# EPS_Flatsat_Module2.net
KiCad netlist of a schematic drawn in EAGLE
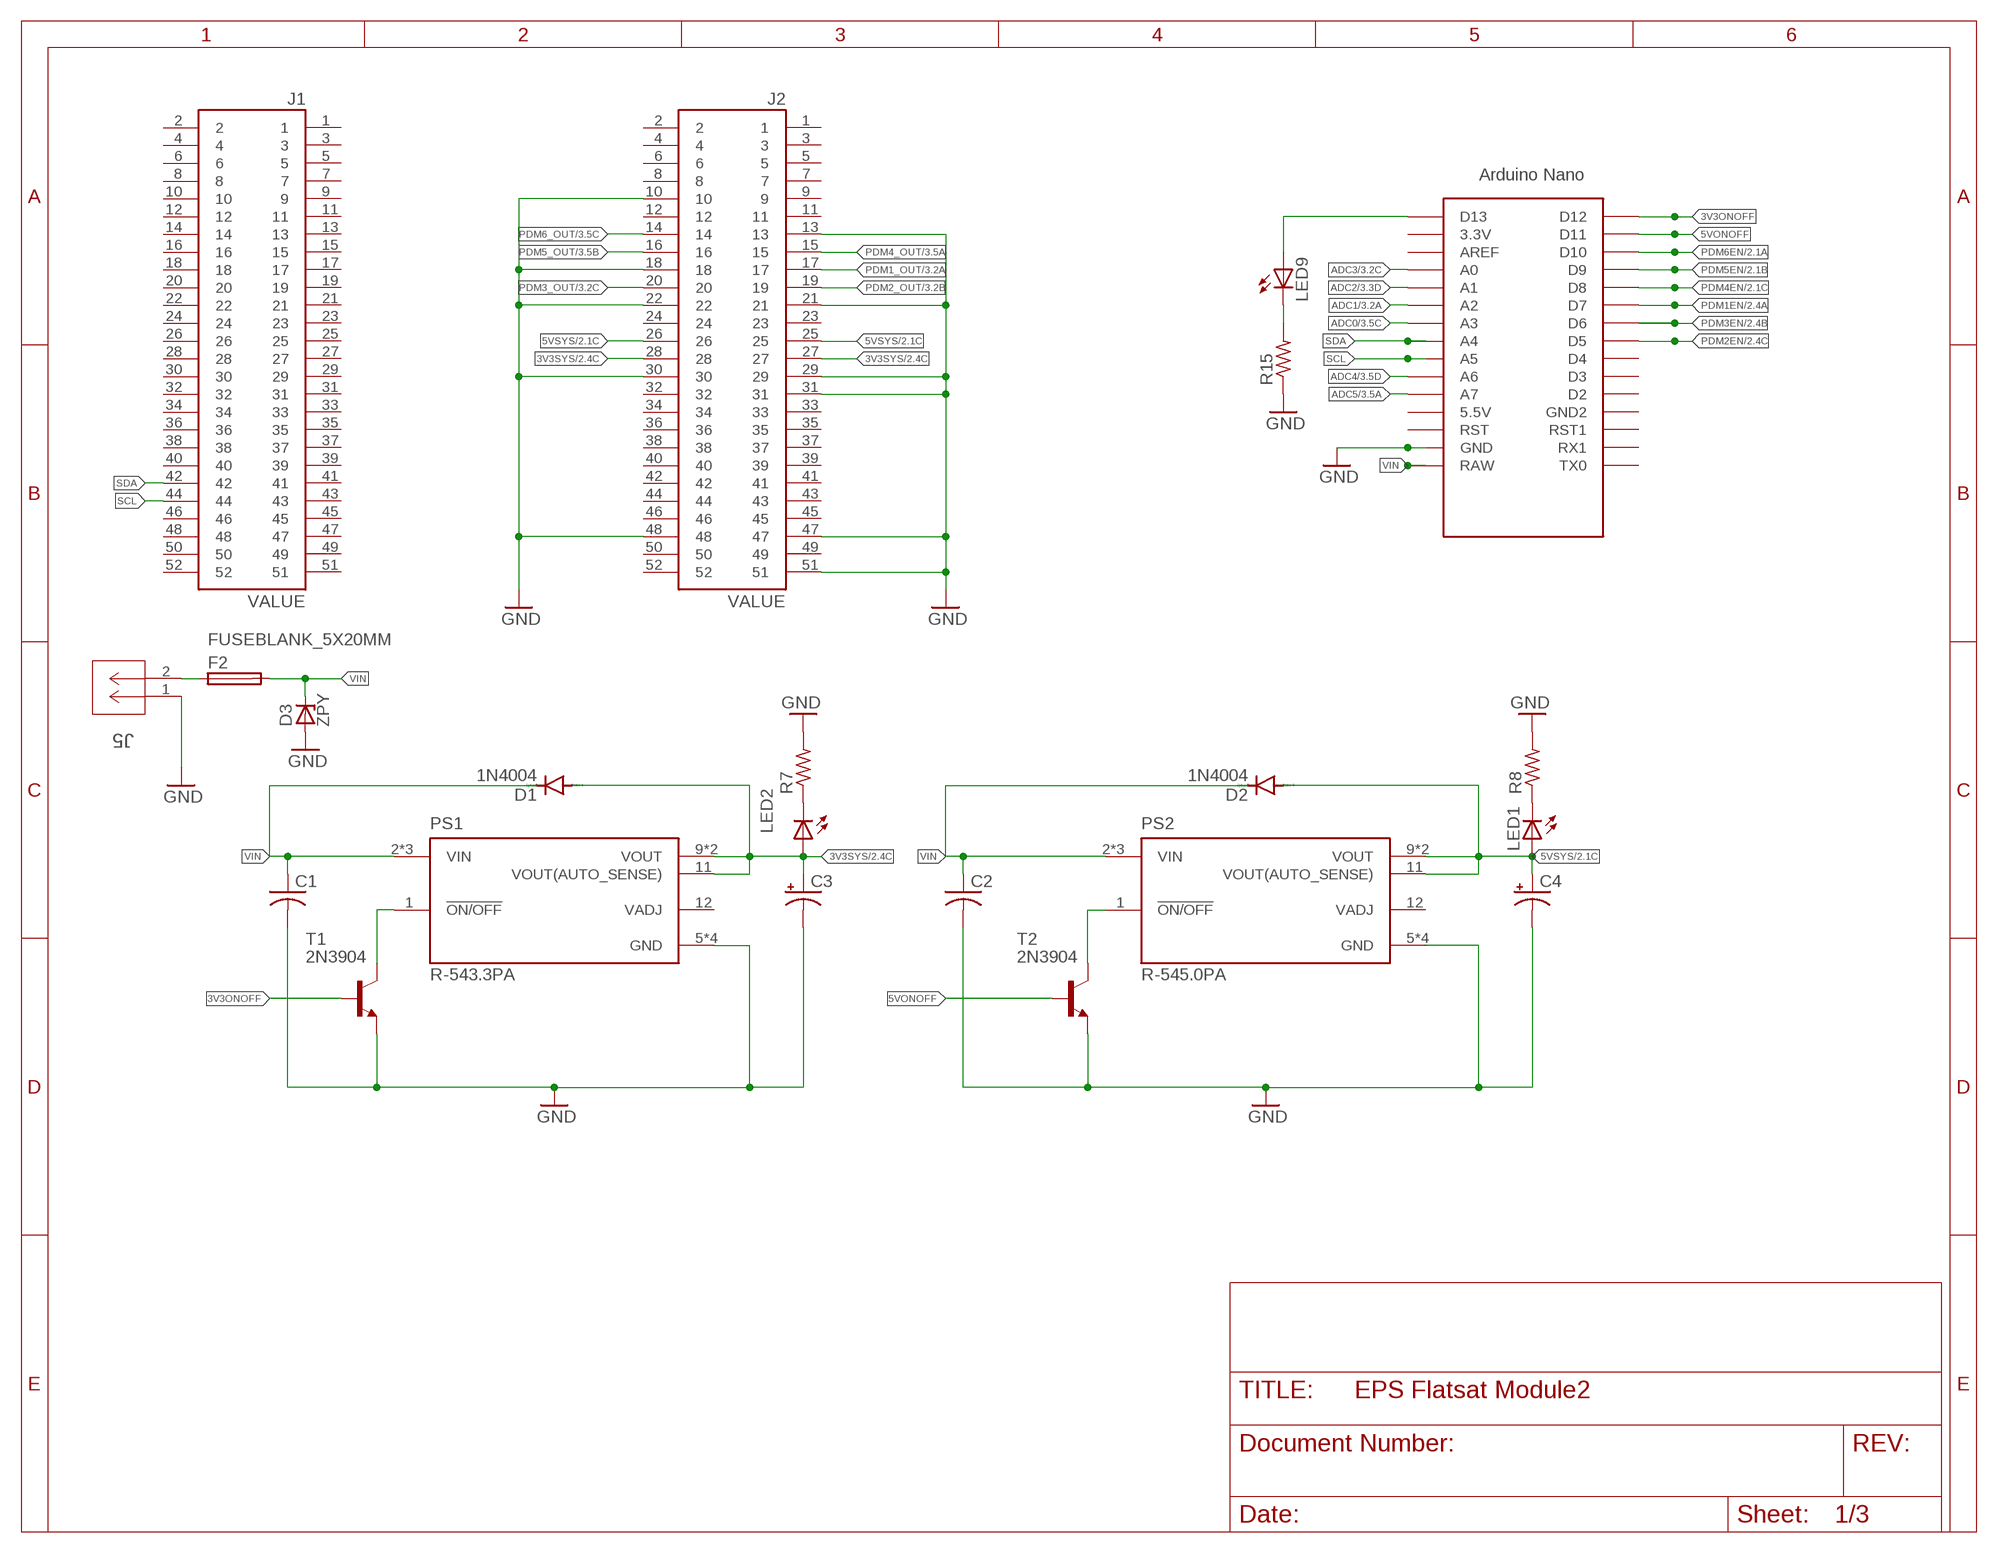
[diagram p0: schematic, sheet 1]
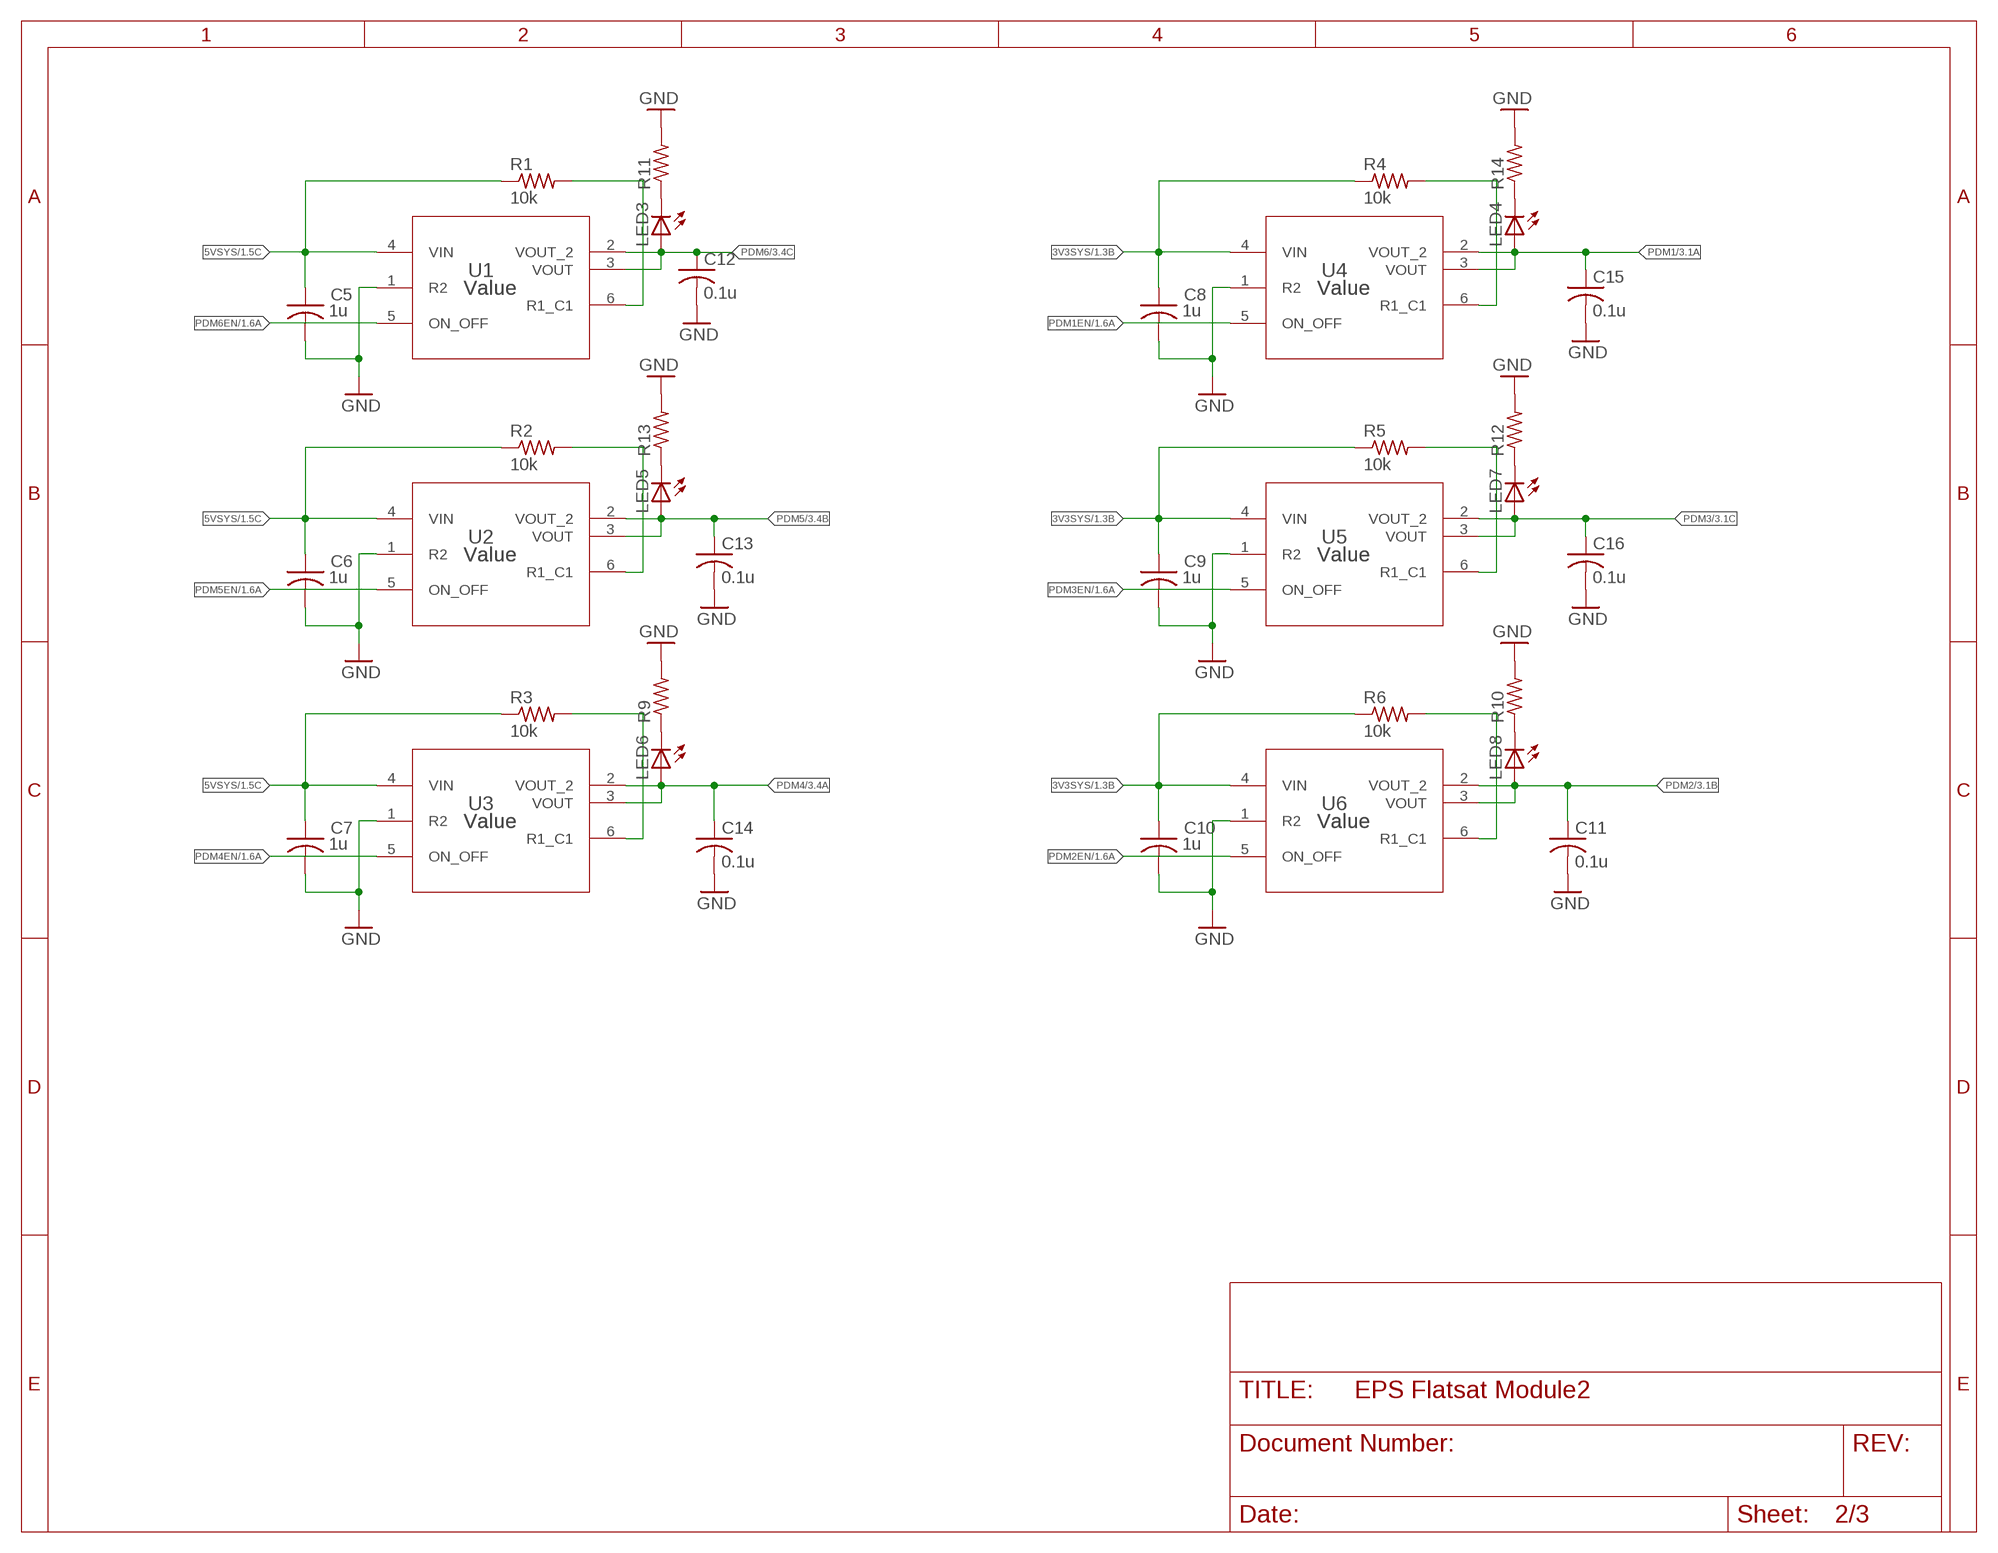
[diagram p1: schematic, sheet 2]
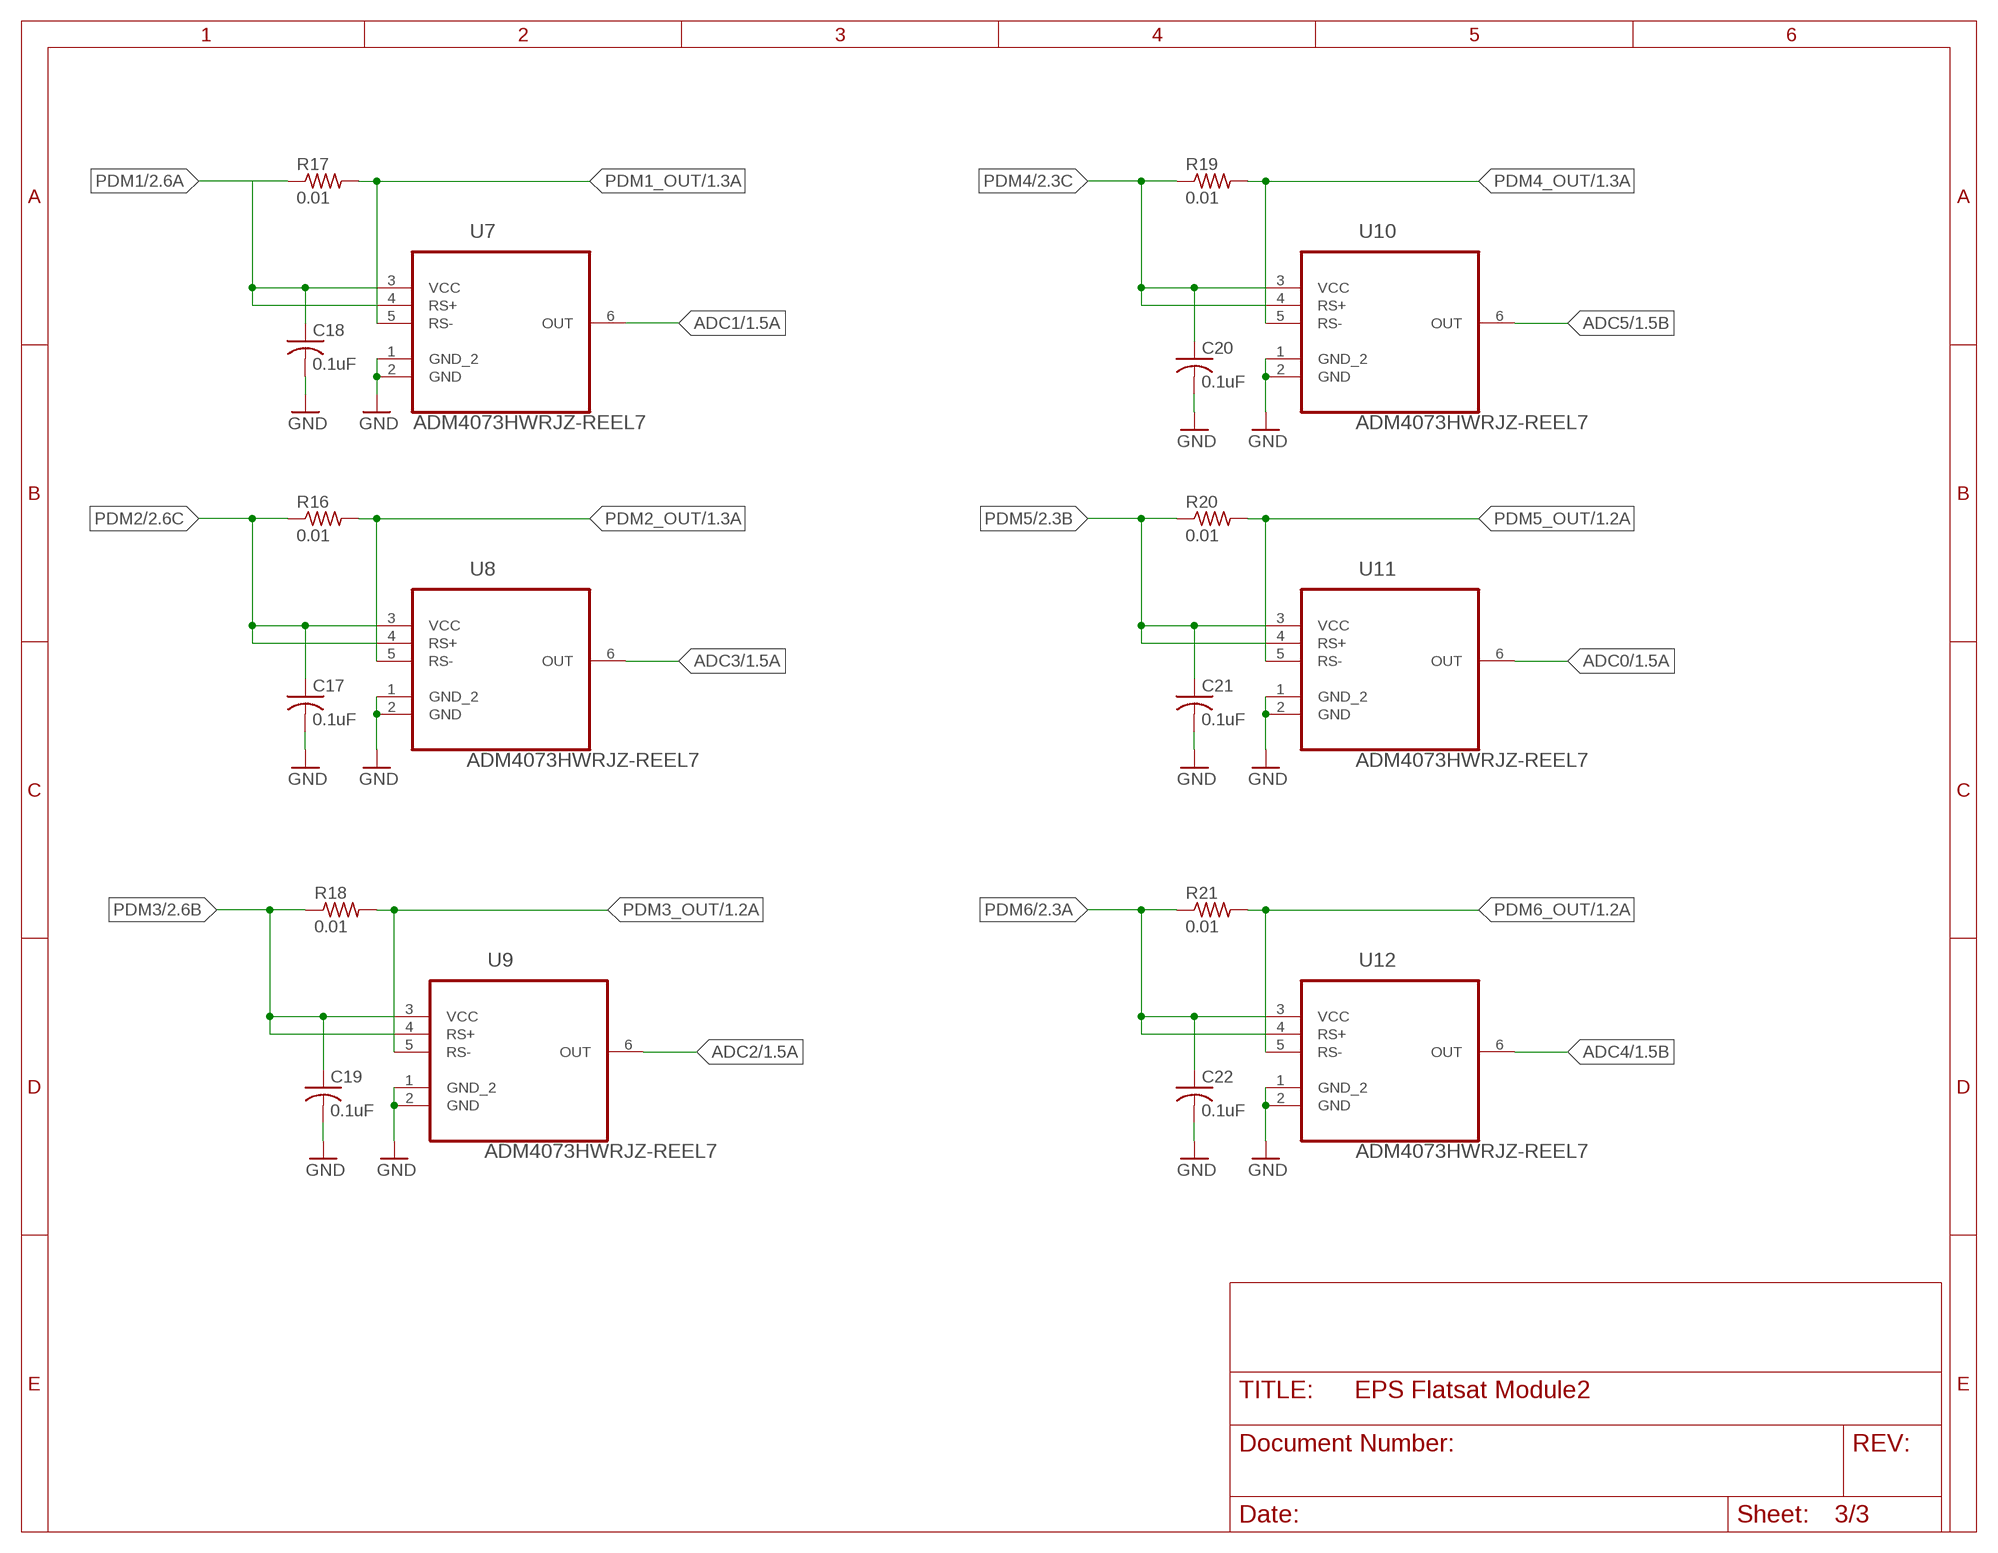
[diagram p2: schematic, sheet 3]

(export (version "E")
  (design (tool "Eeschema 10.0.6"))
  (components
    (comp (ref "C17")
      (value "0.1uF")
      (footprint "eagle-import:C0805")
      (libsource (lib "eagle-import") (part "C-USC0805"))
    )
    (comp (ref "C18")
      (value "0.1uF")
      (footprint "eagle-import:C0805")
      (libsource (lib "eagle-import") (part "C-USC0805"))
    )
    (comp (ref "C19")
      (value "0.1uF")
      (footprint "eagle-import:C0805")
      (libsource (lib "eagle-import") (part "C-USC0805"))
    )
    (comp (ref "C20")
      (value "0.1uF")
      (footprint "eagle-import:C0805")
      (libsource (lib "eagle-import") (part "C-USC0805"))
    )
    (comp (ref "C21")
      (value "0.1uF")
      (footprint "eagle-import:C0805")
      (libsource (lib "eagle-import") (part "C-USC0805"))
    )
    (comp (ref "C22")
      (value "0.1uF")
      (footprint "eagle-import:C0805")
      (libsource (lib "eagle-import") (part "C-USC0805"))
    )
    (comp (ref "R16")
      (value "0.01")
      (footprint "eagle-import:R2512")
      (libsource (lib "eagle-import") (part "R-US_R2512"))
    )
    (comp (ref "R17")
      (value "0.01")
      (footprint "eagle-import:R2512")
      (libsource (lib "eagle-import") (part "R-US_R2512"))
    )
    (comp (ref "R18")
      (value "0.01")
      (footprint "eagle-import:R2512")
      (libsource (lib "eagle-import") (part "R-US_R2512"))
    )
    (comp (ref "R19")
      (value "0.01")
      (footprint "eagle-import:R2512")
      (libsource (lib "eagle-import") (part "R-US_R2512"))
    )
    (comp (ref "R20")
      (value "0.01")
      (footprint "eagle-import:R2512")
      (libsource (lib "eagle-import") (part "R-US_R2512"))
    )
    (comp (ref "R21")
      (value "0.01")
      (footprint "eagle-import:R2512")
      (libsource (lib "eagle-import") (part "R-US_R2512"))
    )
    (comp (ref "U7")
      (value "ADM4073HWRJZ-REEL7")
      (footprint "eagle-import:SOT95P290X145-6N")
      (fields
        (field (name "DIGI-KEY_PART_NUMBER") "ADM4073HWRJZ-REEL7CT-ND")
        (field (name "MF") "Analog Devices")
      )
      (libsource (lib "eagle-import") (part "ADM4073HWRJZ-REEL7"))
    )
    (comp (ref "U8")
      (value "ADM4073HWRJZ-REEL7")
      (footprint "eagle-import:SOT95P290X145-6N")
      (fields
        (field (name "DIGI-KEY_PART_NUMBER") "ADM4073HWRJZ-REEL7CT-ND")
        (field (name "MF") "Analog Devices")
      )
      (libsource (lib "eagle-import") (part "ADM4073HWRJZ-REEL7"))
    )
    (comp (ref "U9")
      (value "ADM4073HWRJZ-REEL7")
      (footprint "eagle-import:SOT95P290X145-6N")
      (fields
        (field (name "DIGI-KEY_PART_NUMBER") "ADM4073HWRJZ-REEL7CT-ND")
        (field (name "MF") "Analog Devices")
      )
      (libsource (lib "eagle-import") (part "ADM4073HWRJZ-REEL7"))
    )
    (comp (ref "U10")
      (value "ADM4073HWRJZ-REEL7")
      (footprint "eagle-import:SOT95P290X145-6N")
      (fields
        (field (name "DIGI-KEY_PART_NUMBER") "ADM4073HWRJZ-REEL7CT-ND")
        (field (name "MF") "Analog Devices")
      )
      (libsource (lib "eagle-import") (part "ADM4073HWRJZ-REEL7"))
    )
    (comp (ref "U11")
      (value "ADM4073HWRJZ-REEL7")
      (footprint "eagle-import:SOT95P290X145-6N")
      (fields
        (field (name "DIGI-KEY_PART_NUMBER") "ADM4073HWRJZ-REEL7CT-ND")
        (field (name "MF") "Analog Devices")
      )
      (libsource (lib "eagle-import") (part "ADM4073HWRJZ-REEL7"))
    )
    (comp (ref "U12")
      (value "ADM4073HWRJZ-REEL7")
      (footprint "eagle-import:SOT95P290X145-6N")
      (fields
        (field (name "DIGI-KEY_PART_NUMBER") "ADM4073HWRJZ-REEL7CT-ND")
        (field (name "MF") "Analog Devices")
      )
      (libsource (lib "eagle-import") (part "ADM4073HWRJZ-REEL7"))
    )
    (comp (ref "C1")
      (value "C-USC0805")
      (footprint "eagle-import:C0805")
      (libsource (lib "eagle-import") (part "C-USC0805"))
    )
    (comp (ref "C2")
      (value "C-USC0805")
      (footprint "eagle-import:C0805")
      (libsource (lib "eagle-import") (part "C-USC0805"))
    )
    (comp (ref "C3")
      (value "CPOL-USE2.5-6")
      (footprint "eagle-import:E2,5-6")
      (libsource (lib "eagle-import") (part "CPOL-USE2.5-6"))
    )
    (comp (ref "C4")
      (value "CPOL-USE2.5-6")
      (footprint "eagle-import:E2,5-6")
      (libsource (lib "eagle-import") (part "CPOL-USE2.5-6"))
    )
    (comp (ref "D1")
      (value "1N4004")
      (footprint "eagle-import:DO41-10")
      (libsource (lib "eagle-import") (part "1N4004"))
    )
    (comp (ref "D2")
      (value "1N4004")
      (footprint "eagle-import:DO41-10")
      (libsource (lib "eagle-import") (part "1N4004"))
    )
    (comp (ref "D3")
      (value "ZPY")
      (footprint "eagle-import:DO41Z10")
      (libsource (lib "eagle-import") (part "ZPY"))
    )
    (comp (ref "F2")
      (value "FUSEBLANK_5X20MM")
      (footprint "eagle-import:FUSE_HOLDER_5X20MM")
      (libsource (lib "eagle-import") (part "FUSEBLANK_5X20MM"))
    )
    (comp (ref "J1")
      (value "ESQ-126-39-G-D")
      (footprint "eagle-import:SAMTEC_ESQ-126-39-G-D")
      (fields (field (name "DIGI-KEY_PART_NUMBER") "SAM10462-ND") (field (name "MF") "Samtec"))
      (libsource (lib "eagle-import") (part "ESQ-126-39-G-D"))
    )
    (comp (ref "J2")
      (value "ESQ-126-39-G-D")
      (footprint "eagle-import:SAMTEC_ESQ-126-39-G-D")
      (fields (field (name "DIGI-KEY_PART_NUMBER") "SAM10462-ND") (field (name "MF") "Samtec"))
      (libsource (lib "eagle-import") (part "ESQ-126-39-G-D"))
    )
    (comp (ref "J5")
      (value "1985881")
      (footprint "eagle-import:CONN_1715022_PXC")
      (fields (field (name "COPYRIGHT") "Copyright (C) 2018 Accelerated Designs. All rights reserved"))
      (libsource (lib "eagle-import") (part "1985881"))
    )
    (comp (ref "LED1")
      (value "LEDCHIPLED_0805")
      (footprint "eagle-import:CHIPLED_0805")
      (libsource (lib "eagle-import") (part "LEDCHIPLED_0805"))
    )
    (comp (ref "LED2")
      (value "LEDCHIPLED_0805")
      (footprint "eagle-import:CHIPLED_0805")
      (libsource (lib "eagle-import") (part "LEDCHIPLED_0805"))
    )
    (comp (ref "LED9")
      (value "LEDCHIP-LED0805")
      (footprint "eagle-import:CHIP-LED0805")
      (libsource (lib "eagle-import") (part "LEDCHIP-LED0805"))
    )
    (comp (ref "PS1")
      (value "R-543.3PA")
      (footprint "eagle-import:CONV_R-543.3PA")
      (fields (field (name "DIGI-KEY_PART_NUMBER") "945-1599-5-ND") (field (name "MF") "Recom Power"))
      (libsource (lib "eagle-import") (part "R-543.3PA"))
    )
    (comp (ref "PS2")
      (value "R-545.0PA")
      (footprint "eagle-import:CONV_R-545.0PA")
      (fields (field (name "DIGI-KEY_PART_NUMBER") "R-545.0PA-ND") (field (name "MF") "Recom Power"))
      (libsource (lib "eagle-import") (part "R-545.0PA"))
    )
    (comp (ref "R7")
      (value "R-US_R0805")
      (footprint "eagle-import:R0805")
      (libsource (lib "eagle-import") (part "R-US_R0805"))
    )
    (comp (ref "R8")
      (value "R-US_R0805")
      (footprint "eagle-import:R0805")
      (libsource (lib "eagle-import") (part "R-US_R0805"))
    )
    (comp (ref "R15")
      (value "R-US_R0805")
      (footprint "eagle-import:R0805")
      (libsource (lib "eagle-import") (part "R-US_R0805"))
    )
    (comp (ref "T1")
      (value "2N3904")
      (footprint "eagle-import:TO92")
      (libsource (lib "eagle-import") (part "2N3904"))
    )
    (comp (ref "T2")
      (value "2N3904")
      (footprint "eagle-import:TO92")
      (libsource (lib "eagle-import") (part "2N3904"))
    )
    (comp (ref "U$1")
      (value "NANO")
      (footprint "eagle-import:NANO")
      (libsource (lib "eagle-import") (part "NANO"))
    )
    (comp (ref "C5")
      (value "1u")
      (footprint "eagle-import:C0805")
      (libsource (lib "eagle-import") (part "C-USC0805"))
    )
    (comp (ref "C6")
      (value "1u")
      (footprint "eagle-import:C0805")
      (libsource (lib "eagle-import") (part "C-USC0805"))
    )
    (comp (ref "C7")
      (value "1u")
      (footprint "eagle-import:C0805")
      (libsource (lib "eagle-import") (part "C-USC0805"))
    )
    (comp (ref "C8")
      (value "1u")
      (footprint "eagle-import:C0805")
      (libsource (lib "eagle-import") (part "C-USC0805"))
    )
    (comp (ref "C9")
      (value "1u")
      (footprint "eagle-import:C0805")
      (libsource (lib "eagle-import") (part "C-USC0805"))
    )
    (comp (ref "C10")
      (value "1u")
      (footprint "eagle-import:C0805")
      (libsource (lib "eagle-import") (part "C-USC0805"))
    )
    (comp (ref "C11")
      (value "0.1u")
      (footprint "eagle-import:C0805")
      (libsource (lib "eagle-import") (part "C-USC0805"))
    )
    (comp (ref "C12")
      (value "0.1u")
      (footprint "eagle-import:C0805")
      (libsource (lib "eagle-import") (part "C-USC0805"))
    )
    (comp (ref "C13")
      (value "0.1u")
      (footprint "eagle-import:C0805")
      (libsource (lib "eagle-import") (part "C-USC0805"))
    )
    (comp (ref "C14")
      (value "0.1u")
      (footprint "eagle-import:C0805")
      (libsource (lib "eagle-import") (part "C-USC0805"))
    )
    (comp (ref "C15")
      (value "0.1u")
      (footprint "eagle-import:C0805")
      (libsource (lib "eagle-import") (part "C-USC0805"))
    )
    (comp (ref "C16")
      (value "0.1u")
      (footprint "eagle-import:C0805")
      (libsource (lib "eagle-import") (part "C-USC0805"))
    )
    (comp (ref "LED3")
      (value "LEDCHIPLED_0805")
      (footprint "eagle-import:CHIPLED_0805")
      (libsource (lib "eagle-import") (part "LEDCHIPLED_0805"))
    )
    (comp (ref "LED4")
      (value "LEDCHIPLED_0805")
      (footprint "eagle-import:CHIPLED_0805")
      (libsource (lib "eagle-import") (part "LEDCHIPLED_0805"))
    )
    (comp (ref "LED5")
      (value "LEDCHIPLED_0805")
      (footprint "eagle-import:CHIPLED_0805")
      (libsource (lib "eagle-import") (part "LEDCHIPLED_0805"))
    )
    (comp (ref "LED6")
      (value "LEDCHIPLED_0805")
      (footprint "eagle-import:CHIPLED_0805")
      (libsource (lib "eagle-import") (part "LEDCHIPLED_0805"))
    )
    (comp (ref "LED7")
      (value "LEDCHIPLED_0805")
      (footprint "eagle-import:CHIPLED_0805")
      (libsource (lib "eagle-import") (part "LEDCHIPLED_0805"))
    )
    (comp (ref "LED8")
      (value "LEDCHIPLED_0805")
      (footprint "eagle-import:CHIPLED_0805")
      (libsource (lib "eagle-import") (part "LEDCHIPLED_0805"))
    )
    (comp (ref "R1")
      (value "10k")
      (footprint "eagle-import:R0805")
      (libsource (lib "eagle-import") (part "R-US_R0805"))
    )
    (comp (ref "R2")
      (value "10k")
      (footprint "eagle-import:R0805")
      (libsource (lib "eagle-import") (part "R-US_R0805"))
    )
    (comp (ref "R3")
      (value "10k")
      (footprint "eagle-import:R0805")
      (libsource (lib "eagle-import") (part "R-US_R0805"))
    )
    (comp (ref "R4")
      (value "10k")
      (footprint "eagle-import:R0805")
      (libsource (lib "eagle-import") (part "R-US_R0805"))
    )
    (comp (ref "R5")
      (value "10k")
      (footprint "eagle-import:R0805")
      (libsource (lib "eagle-import") (part "R-US_R0805"))
    )
    (comp (ref "R6")
      (value "10k")
      (footprint "eagle-import:R0805")
      (libsource (lib "eagle-import") (part "R-US_R0805"))
    )
    (comp (ref "R9")
      (value "R-US_R0805")
      (footprint "eagle-import:R0805")
      (libsource (lib "eagle-import") (part "R-US_R0805"))
    )
    (comp (ref "R10")
      (value "R-US_R0805")
      (footprint "eagle-import:R0805")
      (libsource (lib "eagle-import") (part "R-US_R0805"))
    )
    (comp (ref "R11")
      (value "R-US_R0805")
      (footprint "eagle-import:R0805")
      (libsource (lib "eagle-import") (part "R-US_R0805"))
    )
    (comp (ref "R12")
      (value "R-US_R0805")
      (footprint "eagle-import:R0805")
      (libsource (lib "eagle-import") (part "R-US_R0805"))
    )
    (comp (ref "R13")
      (value "R-US_R0805")
      (footprint "eagle-import:R0805")
      (libsource (lib "eagle-import") (part "R-US_R0805"))
    )
    (comp (ref "R14")
      (value "R-US_R0805")
      (footprint "eagle-import:R0805")
      (libsource (lib "eagle-import") (part "R-US_R0805"))
    )
    (comp (ref "U1")
      (value "Value")
      (footprint "eagle-import:DDC0006A_N")
      (fields (field (name "MANUFACTURER") "Texas Instruments") (field (name "PARTNUMBER") "TPS27081ADDCR"))
      (libsource (lib "eagle-import") (part "TPS27081ADDCR"))
    )
    (comp (ref "U2")
      (value "Value")
      (footprint "eagle-import:DDC0006A_N")
      (fields (field (name "MANUFACTURER") "Texas Instruments") (field (name "PARTNUMBER") "TPS27081ADDCR"))
      (libsource (lib "eagle-import") (part "TPS27081ADDCR"))
    )
    (comp (ref "U3")
      (value "Value")
      (footprint "eagle-import:DDC0006A_N")
      (fields (field (name "MANUFACTURER") "Texas Instruments") (field (name "PARTNUMBER") "TPS27081ADDCR"))
      (libsource (lib "eagle-import") (part "TPS27081ADDCR"))
    )
    (comp (ref "U4")
      (value "Value")
      (footprint "eagle-import:DDC0006A_N")
      (fields (field (name "MANUFACTURER") "Texas Instruments") (field (name "PARTNUMBER") "TPS27081ADDCR"))
      (libsource (lib "eagle-import") (part "TPS27081ADDCR"))
    )
    (comp (ref "U5")
      (value "Value")
      (footprint "eagle-import:DDC0006A_N")
      (fields (field (name "MANUFACTURER") "Texas Instruments") (field (name "PARTNUMBER") "TPS27081ADDCR"))
      (libsource (lib "eagle-import") (part "TPS27081ADDCR"))
    )
    (comp (ref "U6")
      (value "Value")
      (footprint "eagle-import:DDC0006A_N")
      (fields (field (name "MANUFACTURER") "Texas Instruments") (field (name "PARTNUMBER") "TPS27081ADDCR"))
      (libsource (lib "eagle-import") (part "TPS27081ADDCR"))
    )
  )
  (nets
    (net (code "1") (name "3V3ONOFF") (class "Default")
      (node (ref "T1") (pin "2") (pinfunction "B_2") (pintype "passive"))
      (node (ref "U$1") (pin "D12") (pinfunction "D12_D12") (pintype "bidirectional"))
    )
    (net (code "2") (name "3V3SYS") (class "Default")
      (node (ref "C10") (pin "1") (pinfunction "1_1") (pintype "passive"))
      (node (ref "C3") (pin "+") (pinfunction "+_+") (pintype "passive"))
      (node (ref "C8") (pin "1") (pinfunction "1_1") (pintype "passive"))
      (node (ref "C9") (pin "1") (pinfunction "1_1") (pintype "passive"))
      (node (ref "D1") (pin "A") (pinfunction "A_A") (pintype "passive"))
      (node (ref "J2") (pin "27") (pinfunction "27_27") (pintype "passive"))
      (node (ref "J2") (pin "28") (pinfunction "28_28") (pintype "passive"))
      (node (ref "LED2") (pin "A") (pinfunction "A_A") (pintype "passive"))
      (node (ref "PS1") (pin "10") (pinfunction "VOUT_10") (pintype "output"))
      (node (ref "PS1") (pin "11") (pinfunction "VOUT(AUTO_SENSE)_11") (pintype "output"))
      (node (ref "PS1") (pin "9") (pinfunction "VOUT_9") (pintype "output"))
      (node (ref "R4") (pin "1") (pinfunction "1_1") (pintype "passive"))
      (node (ref "R5") (pin "1") (pinfunction "1_1") (pintype "passive"))
      (node (ref "R6") (pin "1") (pinfunction "1_1") (pintype "passive"))
      (node (ref "U4") (pin "4") (pinfunction "VIN_4") (pintype "power_in"))
      (node (ref "U5") (pin "4") (pinfunction "VIN_4") (pintype "power_in"))
      (node (ref "U6") (pin "4") (pinfunction "VIN_4") (pintype "power_in"))
    )
    (net (code "3") (name "5VONOFF") (class "Default")
      (node (ref "T2") (pin "2") (pinfunction "B_2") (pintype "passive"))
      (node (ref "U$1") (pin "D11") (pinfunction "D11_D11") (pintype "bidirectional"))
    )
    (net (code "4") (name "5VSYS") (class "Default")
      (node (ref "C4") (pin "+") (pinfunction "+_+") (pintype "passive"))
      (node (ref "C5") (pin "1") (pinfunction "1_1") (pintype "passive"))
      (node (ref "C6") (pin "1") (pinfunction "1_1") (pintype "passive"))
      (node (ref "C7") (pin "1") (pinfunction "1_1") (pintype "passive"))
      (node (ref "D2") (pin "A") (pinfunction "A_A") (pintype "passive"))
      (node (ref "J2") (pin "25") (pinfunction "25_25") (pintype "passive"))
      (node (ref "J2") (pin "26") (pinfunction "26_26") (pintype "passive"))
      (node (ref "LED1") (pin "A") (pinfunction "A_A") (pintype "passive"))
      (node (ref "PS2") (pin "10") (pinfunction "VOUT_10") (pintype "output"))
      (node (ref "PS2") (pin "11") (pinfunction "VOUT(AUTO_SENSE)_11") (pintype "output"))
      (node (ref "PS2") (pin "9") (pinfunction "VOUT_9") (pintype "output"))
      (node (ref "R1") (pin "1") (pinfunction "1_1") (pintype "passive"))
      (node (ref "R2") (pin "1") (pinfunction "1_1") (pintype "passive"))
      (node (ref "R3") (pin "1") (pinfunction "1_1") (pintype "passive"))
      (node (ref "U1") (pin "4") (pinfunction "VIN_4") (pintype "power_in"))
      (node (ref "U2") (pin "4") (pinfunction "VIN_4") (pintype "power_in"))
      (node (ref "U3") (pin "4") (pinfunction "VIN_4") (pintype "power_in"))
    )
    (net (code "5") (name "ADC0") (class "Default")
      (node (ref "U$1") (pin "A3") (pinfunction "A3_A3") (pintype "bidirectional"))
      (node (ref "U11") (pin "6") (pinfunction "OUT_6") (pintype "output"))
    )
    (net (code "6") (name "ADC1") (class "Default")
      (node (ref "U$1") (pin "A2") (pinfunction "A2_A2") (pintype "bidirectional"))
      (node (ref "U7") (pin "6") (pinfunction "OUT_6") (pintype "output"))
    )
    (net (code "7") (name "ADC2") (class "Default")
      (node (ref "U$1") (pin "A1") (pinfunction "A1_A1") (pintype "bidirectional"))
      (node (ref "U9") (pin "6") (pinfunction "OUT_6") (pintype "output"))
    )
    (net (code "8") (name "ADC3") (class "Default")
      (node (ref "U$1") (pin "A0") (pinfunction "A0_A0") (pintype "bidirectional"))
      (node (ref "U8") (pin "6") (pinfunction "OUT_6") (pintype "output"))
    )
    (net (code "9") (name "ADC4") (class "Default")
      (node (ref "U$1") (pin "A6") (pinfunction "A6_A6") (pintype "bidirectional"))
      (node (ref "U12") (pin "6") (pinfunction "OUT_6") (pintype "output"))
    )
    (net (code "10") (name "ADC5") (class "Default")
      (node (ref "U$1") (pin "A7") (pinfunction "A7_A7") (pintype "bidirectional"))
      (node (ref "U10") (pin "6") (pinfunction "OUT_6") (pintype "output"))
    )
    (net (code "11") (name "GND") (class "Default")
      (node (ref "C1") (pin "2") (pinfunction "2_2") (pintype "passive"))
      (node (ref "C10") (pin "2") (pinfunction "2_2") (pintype "passive"))
      (node (ref "C11") (pin "2") (pinfunction "2_2") (pintype "passive"))
      (node (ref "C12") (pin "2") (pinfunction "2_2") (pintype "passive"))
      (node (ref "C13") (pin "2") (pinfunction "2_2") (pintype "passive"))
      (node (ref "C14") (pin "2") (pinfunction "2_2") (pintype "passive"))
      (node (ref "C15") (pin "2") (pinfunction "2_2") (pintype "passive"))
      (node (ref "C16") (pin "2") (pinfunction "2_2") (pintype "passive"))
      (node (ref "C17") (pin "2") (pinfunction "2_2") (pintype "passive"))
      (node (ref "C18") (pin "2") (pinfunction "2_2") (pintype "passive"))
      (node (ref "C19") (pin "2") (pinfunction "2_2") (pintype "passive"))
      (node (ref "C2") (pin "2") (pinfunction "2_2") (pintype "passive"))
      (node (ref "C20") (pin "2") (pinfunction "2_2") (pintype "passive"))
      (node (ref "C21") (pin "2") (pinfunction "2_2") (pintype "passive"))
      (node (ref "C22") (pin "2") (pinfunction "2_2") (pintype "passive"))
      (node (ref "C3") (pin "-") (pinfunction "-_-") (pintype "passive"))
      (node (ref "C4") (pin "-") (pinfunction "-_-") (pintype "passive"))
      (node (ref "C5") (pin "2") (pinfunction "2_2") (pintype "passive"))
      (node (ref "C6") (pin "2") (pinfunction "2_2") (pintype "passive"))
      (node (ref "C7") (pin "2") (pinfunction "2_2") (pintype "passive"))
      (node (ref "C8") (pin "2") (pinfunction "2_2") (pintype "passive"))
      (node (ref "C9") (pin "2") (pinfunction "2_2") (pintype "passive"))
      (node (ref "D3") (pin "A") (pinfunction "A_A") (pintype "passive"))
      (node (ref "J2") (pin "10") (pinfunction "10_10") (pintype "passive"))
      (node (ref "J2") (pin "13") (pinfunction "13_13") (pintype "passive"))
      (node (ref "J2") (pin "18") (pinfunction "18_18") (pintype "passive"))
      (node (ref "J2") (pin "21") (pinfunction "21_21") (pintype "passive"))
      (node (ref "J2") (pin "22") (pinfunction "22_22") (pintype "passive"))
      (node (ref "J2") (pin "29") (pinfunction "29_29") (pintype "passive"))
      (node (ref "J2") (pin "30") (pinfunction "30_30") (pintype "passive"))
      (node (ref "J2") (pin "31") (pinfunction "31_31") (pintype "passive"))
      (node (ref "J2") (pin "47") (pinfunction "47_47") (pintype "passive"))
      (node (ref "J2") (pin "48") (pinfunction "48_48") (pintype "passive"))
      (node (ref "J2") (pin "51") (pinfunction "51_51") (pintype "passive"))
      (node (ref "J5") (pin "1") (pinfunction "1_1") (pintype "passive"))
      (node (ref "PS1") (pin "5") (pinfunction "GND_5") (pintype "power_in"))
      (node (ref "PS1") (pin "6") (pinfunction "GND_6") (pintype "power_in"))
      (node (ref "PS1") (pin "7") (pinfunction "GND_7") (pintype "power_in"))
      (node (ref "PS1") (pin "8") (pinfunction "GND_8") (pintype "power_in"))
      (node (ref "PS2") (pin "5") (pinfunction "GND_5") (pintype "power_in"))
      (node (ref "PS2") (pin "6") (pinfunction "GND_6") (pintype "power_in"))
      (node (ref "PS2") (pin "7") (pinfunction "GND_7") (pintype "power_in"))
      (node (ref "PS2") (pin "8") (pinfunction "GND_8") (pintype "power_in"))
      (node (ref "R10") (pin "2") (pinfunction "2_2") (pintype "passive"))
      (node (ref "R11") (pin "2") (pinfunction "2_2") (pintype "passive"))
      (node (ref "R12") (pin "2") (pinfunction "2_2") (pintype "passive"))
      (node (ref "R13") (pin "2") (pinfunction "2_2") (pintype "passive"))
      (node (ref "R14") (pin "2") (pinfunction "2_2") (pintype "passive"))
      (node (ref "R15") (pin "1") (pinfunction "1_1") (pintype "passive"))
      (node (ref "R7") (pin "2") (pinfunction "2_2") (pintype "passive"))
      (node (ref "R8") (pin "2") (pinfunction "2_2") (pintype "passive"))
      (node (ref "R9") (pin "2") (pinfunction "2_2") (pintype "passive"))
      (node (ref "T1") (pin "3") (pinfunction "E_3") (pintype "passive"))
      (node (ref "T2") (pin "3") (pinfunction "E_3") (pintype "passive"))
      (node (ref "U$1") (pin "GND") (pinfunction "GND_GND") (pintype "bidirectional"))
      (node (ref "U1") (pin "1") (pinfunction "R2_1") (pintype "input"))
      (node (ref "U10") (pin "1") (pinfunction "GND_2_1") (pintype "passive"))
      (node (ref "U10") (pin "2") (pinfunction "GND_2") (pintype "passive"))
      (node (ref "U11") (pin "1") (pinfunction "GND_2_1") (pintype "passive"))
      (node (ref "U11") (pin "2") (pinfunction "GND_2") (pintype "passive"))
      (node (ref "U12") (pin "1") (pinfunction "GND_2_1") (pintype "passive"))
      (node (ref "U12") (pin "2") (pinfunction "GND_2") (pintype "passive"))
      (node (ref "U2") (pin "1") (pinfunction "R2_1") (pintype "input"))
      (node (ref "U3") (pin "1") (pinfunction "R2_1") (pintype "input"))
      (node (ref "U4") (pin "1") (pinfunction "R2_1") (pintype "input"))
      (node (ref "U5") (pin "1") (pinfunction "R2_1") (pintype "input"))
      (node (ref "U6") (pin "1") (pinfunction "R2_1") (pintype "input"))
      (node (ref "U7") (pin "1") (pinfunction "GND_2_1") (pintype "passive"))
      (node (ref "U7") (pin "2") (pinfunction "GND_2") (pintype "passive"))
      (node (ref "U8") (pin "1") (pinfunction "GND_2_1") (pintype "passive"))
      (node (ref "U8") (pin "2") (pinfunction "GND_2") (pintype "passive"))
      (node (ref "U9") (pin "1") (pinfunction "GND_2_1") (pintype "passive"))
      (node (ref "U9") (pin "2") (pinfunction "GND_2") (pintype "passive"))
    )
    (net (code "12") (name "Net-(F2-Pad1)") (class "Default")
      (node (ref "F2") (pin "1") (pinfunction "1_1") (pintype "passive"))
      (node (ref "J5") (pin "2") (pinfunction "2_2") (pintype "passive"))
    )
    (net (code "13") (name "Net-(LED1-PadC)") (class "Default")
      (node (ref "LED1") (pin "C") (pinfunction "C_C") (pintype "passive"))
      (node (ref "R8") (pin "1") (pinfunction "1_1") (pintype "passive"))
    )
    (net (code "14") (name "Net-(LED2-PadC)") (class "Default")
      (node (ref "LED2") (pin "C") (pinfunction "C_C") (pintype "passive"))
      (node (ref "R7") (pin "1") (pinfunction "1_1") (pintype "passive"))
    )
    (net (code "15") (name "Net-(LED3-PadC)") (class "Default")
      (node (ref "LED3") (pin "C") (pinfunction "C_C") (pintype "passive"))
      (node (ref "R11") (pin "1") (pinfunction "1_1") (pintype "passive"))
    )
    (net (code "16") (name "Net-(LED4-PadC)") (class "Default")
      (node (ref "LED4") (pin "C") (pinfunction "C_C") (pintype "passive"))
      (node (ref "R14") (pin "1") (pinfunction "1_1") (pintype "passive"))
    )
    (net (code "17") (name "Net-(LED5-PadC)") (class "Default")
      (node (ref "LED5") (pin "C") (pinfunction "C_C") (pintype "passive"))
      (node (ref "R13") (pin "1") (pinfunction "1_1") (pintype "passive"))
    )
    (net (code "18") (name "Net-(LED6-PadC)") (class "Default")
      (node (ref "LED6") (pin "C") (pinfunction "C_C") (pintype "passive"))
      (node (ref "R9") (pin "1") (pinfunction "1_1") (pintype "passive"))
    )
    (net (code "19") (name "Net-(LED7-PadC)") (class "Default")
      (node (ref "LED7") (pin "C") (pinfunction "C_C") (pintype "passive"))
      (node (ref "R12") (pin "1") (pinfunction "1_1") (pintype "passive"))
    )
    (net (code "20") (name "Net-(LED8-PadC)") (class "Default")
      (node (ref "LED8") (pin "C") (pinfunction "C_C") (pintype "passive"))
      (node (ref "R10") (pin "1") (pinfunction "1_1") (pintype "passive"))
    )
    (net (code "21") (name "Net-(LED9-PadA)") (class "Default")
      (node (ref "LED9") (pin "A") (pinfunction "A_A") (pintype "passive"))
      (node (ref "U$1") (pin "D13") (pinfunction "D13_D13") (pintype "bidirectional"))
    )
    (net (code "22") (name "Net-(LED9-PadC)") (class "Default")
      (node (ref "LED9") (pin "C") (pinfunction "C_C") (pintype "passive"))
      (node (ref "R15") (pin "2") (pinfunction "2_2") (pintype "passive"))
    )
    (net (code "23") (name "Net-(PS1-~{ON{slash}OFF})") (class "Default")
      (node (ref "PS1") (pin "1") (pinfunction "~{ON/OFF}_1") (pintype "input"))
      (node (ref "T1") (pin "1") (pinfunction "C_1") (pintype "passive"))
    )
    (net (code "24") (name "Net-(PS2-~{ON{slash}OFF})") (class "Default")
      (node (ref "PS2") (pin "1") (pinfunction "~{ON/OFF}_1") (pintype "input"))
      (node (ref "T2") (pin "1") (pinfunction "C_1") (pintype "passive"))
    )
    (net (code "25") (name "Net-(U1-R1_C1)") (class "Default")
      (node (ref "R1") (pin "2") (pinfunction "2_2") (pintype "passive"))
      (node (ref "U1") (pin "6") (pinfunction "R1_C1_6") (pintype "input"))
    )
    (net (code "26") (name "Net-(U2-R1_C1)") (class "Default")
      (node (ref "R2") (pin "2") (pinfunction "2_2") (pintype "passive"))
      (node (ref "U2") (pin "6") (pinfunction "R1_C1_6") (pintype "input"))
    )
    (net (code "27") (name "Net-(U3-R1_C1)") (class "Default")
      (node (ref "R3") (pin "2") (pinfunction "2_2") (pintype "passive"))
      (node (ref "U3") (pin "6") (pinfunction "R1_C1_6") (pintype "input"))
    )
    (net (code "28") (name "Net-(U4-R1_C1)") (class "Default")
      (node (ref "R4") (pin "2") (pinfunction "2_2") (pintype "passive"))
      (node (ref "U4") (pin "6") (pinfunction "R1_C1_6") (pintype "input"))
    )
    (net (code "29") (name "Net-(U5-R1_C1)") (class "Default")
      (node (ref "R5") (pin "2") (pinfunction "2_2") (pintype "passive"))
      (node (ref "U5") (pin "6") (pinfunction "R1_C1_6") (pintype "input"))
    )
    (net (code "30") (name "Net-(U6-R1_C1)") (class "Default")
      (node (ref "R6") (pin "2") (pinfunction "2_2") (pintype "passive"))
      (node (ref "U6") (pin "6") (pinfunction "R1_C1_6") (pintype "input"))
    )
    (net (code "31") (name "PDM1") (class "Default")
      (node (ref "C15") (pin "1") (pinfunction "1_1") (pintype "passive"))
      (node (ref "C18") (pin "1") (pinfunction "1_1") (pintype "passive"))
      (node (ref "LED4") (pin "A") (pinfunction "A_A") (pintype "passive"))
      (node (ref "R17") (pin "1") (pinfunction "1_1") (pintype "passive"))
      (node (ref "U4") (pin "2") (pinfunction "VOUT_2_2") (pintype "power_in"))
      (node (ref "U4") (pin "3") (pinfunction "VOUT_3") (pintype "power_in"))
      (node (ref "U7") (pin "3") (pinfunction "VCC_3") (pintype "power_in"))
      (node (ref "U7") (pin "4") (pinfunction "RS+_4") (pintype "passive"))
    )
    (net (code "32") (name "PDM1EN") (class "Default")
      (node (ref "U$1") (pin "D7") (pinfunction "D7_D7") (pintype "bidirectional"))
      (node (ref "U4") (pin "5") (pinfunction "ON_OFF_5") (pintype "input"))
    )
    (net (code "33") (name "PDM1_OUT") (class "Default")
      (node (ref "J2") (pin "17") (pinfunction "17_17") (pintype "passive"))
      (node (ref "R17") (pin "2") (pinfunction "2_2") (pintype "passive"))
      (node (ref "U7") (pin "5") (pinfunction "RS-_5") (pintype "passive"))
    )
    (net (code "34") (name "PDM2") (class "Default")
      (node (ref "C11") (pin "1") (pinfunction "1_1") (pintype "passive"))
      (node (ref "C17") (pin "1") (pinfunction "1_1") (pintype "passive"))
      (node (ref "LED8") (pin "A") (pinfunction "A_A") (pintype "passive"))
      (node (ref "R16") (pin "1") (pinfunction "1_1") (pintype "passive"))
      (node (ref "U6") (pin "2") (pinfunction "VOUT_2_2") (pintype "power_in"))
      (node (ref "U6") (pin "3") (pinfunction "VOUT_3") (pintype "power_in"))
      (node (ref "U8") (pin "3") (pinfunction "VCC_3") (pintype "power_in"))
      (node (ref "U8") (pin "4") (pinfunction "RS+_4") (pintype "passive"))
    )
    (net (code "35") (name "PDM2EN") (class "Default")
      (node (ref "U$1") (pin "D5") (pinfunction "D5_D5") (pintype "bidirectional"))
      (node (ref "U6") (pin "5") (pinfunction "ON_OFF_5") (pintype "input"))
    )
    (net (code "36") (name "PDM2_OUT") (class "Default")
      (node (ref "J2") (pin "19") (pinfunction "19_19") (pintype "passive"))
      (node (ref "R16") (pin "2") (pinfunction "2_2") (pintype "passive"))
      (node (ref "U8") (pin "5") (pinfunction "RS-_5") (pintype "passive"))
    )
    (net (code "37") (name "PDM3") (class "Default")
      (node (ref "C16") (pin "1") (pinfunction "1_1") (pintype "passive"))
      (node (ref "C19") (pin "1") (pinfunction "1_1") (pintype "passive"))
      (node (ref "LED7") (pin "A") (pinfunction "A_A") (pintype "passive"))
      (node (ref "R18") (pin "1") (pinfunction "1_1") (pintype "passive"))
      (node (ref "U5") (pin "2") (pinfunction "VOUT_2_2") (pintype "power_in"))
      (node (ref "U5") (pin "3") (pinfunction "VOUT_3") (pintype "power_in"))
      (node (ref "U9") (pin "3") (pinfunction "VCC_3") (pintype "power_in"))
      (node (ref "U9") (pin "4") (pinfunction "RS+_4") (pintype "passive"))
    )
    (net (code "38") (name "PDM3EN") (class "Default")
      (node (ref "U$1") (pin "D6") (pinfunction "D6_D6") (pintype "bidirectional"))
      (node (ref "U5") (pin "5") (pinfunction "ON_OFF_5") (pintype "input"))
    )
    (net (code "39") (name "PDM3_OUT") (class "Default")
      (node (ref "J2") (pin "20") (pinfunction "20_20") (pintype "passive"))
      (node (ref "R18") (pin "2") (pinfunction "2_2") (pintype "passive"))
      (node (ref "U9") (pin "5") (pinfunction "RS-_5") (pintype "passive"))
    )
    (net (code "40") (name "PDM4") (class "Default")
      (node (ref "C14") (pin "1") (pinfunction "1_1") (pintype "passive"))
      (node (ref "C20") (pin "1") (pinfunction "1_1") (pintype "passive"))
      (node (ref "LED6") (pin "A") (pinfunction "A_A") (pintype "passive"))
      (node (ref "R19") (pin "1") (pinfunction "1_1") (pintype "passive"))
      (node (ref "U10") (pin "3") (pinfunction "VCC_3") (pintype "power_in"))
      (node (ref "U10") (pin "4") (pinfunction "RS+_4") (pintype "passive"))
      (node (ref "U3") (pin "2") (pinfunction "VOUT_2_2") (pintype "power_in"))
      (node (ref "U3") (pin "3") (pinfunction "VOUT_3") (pintype "power_in"))
    )
    (net (code "41") (name "PDM4EN") (class "Default")
      (node (ref "U$1") (pin "D8") (pinfunction "D8_D8") (pintype "bidirectional"))
      (node (ref "U3") (pin "5") (pinfunction "ON_OFF_5") (pintype "input"))
    )
    (net (code "42") (name "PDM4_OUT") (class "Default")
      (node (ref "J2") (pin "15") (pinfunction "15_15") (pintype "passive"))
      (node (ref "R19") (pin "2") (pinfunction "2_2") (pintype "passive"))
      (node (ref "U10") (pin "5") (pinfunction "RS-_5") (pintype "passive"))
    )
    (net (code "43") (name "PDM5") (class "Default")
      (node (ref "C13") (pin "1") (pinfunction "1_1") (pintype "passive"))
      (node (ref "C21") (pin "1") (pinfunction "1_1") (pintype "passive"))
      (node (ref "LED5") (pin "A") (pinfunction "A_A") (pintype "passive"))
      (node (ref "R20") (pin "1") (pinfunction "1_1") (pintype "passive"))
      (node (ref "U11") (pin "3") (pinfunction "VCC_3") (pintype "power_in"))
      (node (ref "U11") (pin "4") (pinfunction "RS+_4") (pintype "passive"))
      (node (ref "U2") (pin "2") (pinfunction "VOUT_2_2") (pintype "power_in"))
      (node (ref "U2") (pin "3") (pinfunction "VOUT_3") (pintype "power_in"))
    )
    (net (code "44") (name "PDM5EN") (class "Default")
      (node (ref "U$1") (pin "D9") (pinfunction "D9_D9") (pintype "bidirectional"))
      (node (ref "U2") (pin "5") (pinfunction "ON_OFF_5") (pintype "input"))
    )
    (net (code "45") (name "PDM5_OUT") (class "Default")
      (node (ref "J2") (pin "16") (pinfunction "16_16") (pintype "passive"))
      (node (ref "R20") (pin "2") (pinfunction "2_2") (pintype "passive"))
      (node (ref "U11") (pin "5") (pinfunction "RS-_5") (pintype "passive"))
    )
    (net (code "46") (name "PDM6") (class "Default")
      (node (ref "C12") (pin "1") (pinfunction "1_1") (pintype "passive"))
      (node (ref "C22") (pin "1") (pinfunction "1_1") (pintype "passive"))
      (node (ref "LED3") (pin "A") (pinfunction "A_A") (pintype "passive"))
      (node (ref "R21") (pin "1") (pinfunction "1_1") (pintype "passive"))
      (node (ref "U1") (pin "2") (pinfunction "VOUT_2_2") (pintype "power_in"))
      (node (ref "U1") (pin "3") (pinfunction "VOUT_3") (pintype "power_in"))
      (node (ref "U12") (pin "3") (pinfunction "VCC_3") (pintype "power_in"))
      (node (ref "U12") (pin "4") (pinfunction "RS+_4") (pintype "passive"))
    )
    (net (code "47") (name "PDM6EN") (class "Default")
      (node (ref "U$1") (pin "D10") (pinfunction "D10_D10") (pintype "bidirectional"))
      (node (ref "U1") (pin "5") (pinfunction "ON_OFF_5") (pintype "input"))
    )
    (net (code "48") (name "PDM6_OUT") (class "Default")
      (node (ref "J2") (pin "14") (pinfunction "14_14") (pintype "passive"))
      (node (ref "R21") (pin "2") (pinfunction "2_2") (pintype "passive"))
      (node (ref "U12") (pin "5") (pinfunction "RS-_5") (pintype "passive"))
    )
    (net (code "49") (name "SCL") (class "Default")
      (node (ref "J1") (pin "44") (pinfunction "44_44") (pintype "passive"))
      (node (ref "U$1") (pin "A5") (pinfunction "A5_A5") (pintype "bidirectional"))
    )
    (net (code "50") (name "SDA") (class "Default")
      (node (ref "J1") (pin "42") (pinfunction "42_42") (pintype "passive"))
      (node (ref "U$1") (pin "A4") (pinfunction "A4_A4") (pintype "bidirectional"))
    )
    (net (code "51") (name "VIN") (class "Default")
      (node (ref "C1") (pin "1") (pinfunction "1_1") (pintype "passive"))
      (node (ref "C2") (pin "1") (pinfunction "1_1") (pintype "passive"))
      (node (ref "D1") (pin "C") (pinfunction "C_C") (pintype "passive"))
      (node (ref "D2") (pin "C") (pinfunction "C_C") (pintype "passive"))
      (node (ref "D3") (pin "C") (pinfunction "C_C") (pintype "passive"))
      (node (ref "F2") (pin "2") (pinfunction "2_2") (pintype "passive"))
      (node (ref "PS1") (pin "2") (pinfunction "VIN_2") (pintype "input"))
      (node (ref "PS1") (pin "3") (pinfunction "VIN_3") (pintype "input"))
      (node (ref "PS1") (pin "4") (pinfunction "VIN_4") (pintype "input"))
      (node (ref "PS2") (pin "2") (pinfunction "VIN_2") (pintype "input"))
      (node (ref "PS2") (pin "3") (pinfunction "VIN_3") (pintype "input"))
      (node (ref "PS2") (pin "4") (pinfunction "VIN_4") (pintype "input"))
      (node (ref "U$1") (pin "RAW") (pinfunction "RAW_RAW") (pintype "bidirectional"))
    )
    (net (code "52") (name "unconnected-(J1-Pad1)") (class "Default")
      (node (ref "J1") (pin "1") (pinfunction "1_1") (pintype "passive"))
    )
    (net (code "53") (name "unconnected-(J1-Pad2)") (class "Default")
      (node (ref "J1") (pin "2") (pinfunction "2_2") (pintype "passive"))
    )
    (net (code "54") (name "unconnected-(J1-Pad3)") (class "Default")
      (node (ref "J1") (pin "3") (pinfunction "3_3") (pintype "passive"))
    )
    (net (code "55") (name "unconnected-(J1-Pad4)") (class "Default")
      (node (ref "J1") (pin "4") (pinfunction "4_4") (pintype "passive"))
    )
    (net (code "56") (name "unconnected-(J1-Pad5)") (class "Default")
      (node (ref "J1") (pin "5") (pinfunction "5_5") (pintype "passive"))
    )
    (net (code "57") (name "unconnected-(J1-Pad6)") (class "Default")
      (node (ref "J1") (pin "6") (pinfunction "6_6") (pintype "passive"))
    )
    (net (code "58") (name "unconnected-(J1-Pad7)") (class "Default")
      (node (ref "J1") (pin "7") (pinfunction "7_7") (pintype "passive"))
    )
    (net (code "59") (name "unconnected-(J1-Pad8)") (class "Default")
      (node (ref "J1") (pin "8") (pinfunction "8_8") (pintype "passive"))
    )
    (net (code "60") (name "unconnected-(J1-Pad9)") (class "Default")
      (node (ref "J1") (pin "9") (pinfunction "9_9") (pintype "passive"))
    )
    (net (code "61") (name "unconnected-(J1-Pad10)") (class "Default")
      (node (ref "J1") (pin "10") (pinfunction "10_10") (pintype "passive"))
    )
    (net (code "62") (name "unconnected-(J1-Pad11)") (class "Default")
      (node (ref "J1") (pin "11") (pinfunction "11_11") (pintype "passive"))
    )
    (net (code "63") (name "unconnected-(J1-Pad12)") (class "Default")
      (node (ref "J1") (pin "12") (pinfunction "12_12") (pintype "passive"))
    )
    (net (code "64") (name "unconnected-(J1-Pad13)") (class "Default")
      (node (ref "J1") (pin "13") (pinfunction "13_13") (pintype "passive"))
    )
    (net (code "65") (name "unconnected-(J1-Pad14)") (class "Default")
      (node (ref "J1") (pin "14") (pinfunction "14_14") (pintype "passive"))
    )
    (net (code "66") (name "unconnected-(J1-Pad15)") (class "Default")
      (node (ref "J1") (pin "15") (pinfunction "15_15") (pintype "passive"))
    )
    (net (code "67") (name "unconnected-(J1-Pad16)") (class "Default")
      (node (ref "J1") (pin "16") (pinfunction "16_16") (pintype "passive"))
    )
    (net (code "68") (name "unconnected-(J1-Pad17)") (class "Default")
      (node (ref "J1") (pin "17") (pinfunction "17_17") (pintype "passive"))
    )
    (net (code "69") (name "unconnected-(J1-Pad18)") (class "Default")
      (node (ref "J1") (pin "18") (pinfunction "18_18") (pintype "passive"))
    )
    (net (code "70") (name "unconnected-(J1-Pad19)") (class "Default")
      (node (ref "J1") (pin "19") (pinfunction "19_19") (pintype "passive"))
    )
    (net (code "71") (name "unconnected-(J1-Pad20)") (class "Default")
      (node (ref "J1") (pin "20") (pinfunction "20_20") (pintype "passive"))
    )
    (net (code "72") (name "unconnected-(J1-Pad21)") (class "Default")
      (node (ref "J1") (pin "21") (pinfunction "21_21") (pintype "passive"))
    )
    (net (code "73") (name "unconnected-(J1-Pad22)") (class "Default")
      (node (ref "J1") (pin "22") (pinfunction "22_22") (pintype "passive"))
    )
    (net (code "74") (name "unconnected-(J1-Pad23)") (class "Default")
      (node (ref "J1") (pin "23") (pinfunction "23_23") (pintype "passive"))
    )
    (net (code "75") (name "unconnected-(J1-Pad24)") (class "Default")
      (node (ref "J1") (pin "24") (pinfunction "24_24") (pintype "passive"))
    )
    (net (code "76") (name "unconnected-(J1-Pad25)") (class "Default")
      (node (ref "J1") (pin "25") (pinfunction "25_25") (pintype "passive"))
    )
    (net (code "77") (name "unconnected-(J1-Pad26)") (class "Default")
      (node (ref "J1") (pin "26") (pinfunction "26_26") (pintype "passive"))
    )
    (net (code "78") (name "unconnected-(J1-Pad27)") (class "Default")
      (node (ref "J1") (pin "27") (pinfunction "27_27") (pintype "passive"))
    )
    (net (code "79") (name "unconnected-(J1-Pad28)") (class "Default")
      (node (ref "J1") (pin "28") (pinfunction "28_28") (pintype "passive"))
    )
    (net (code "80") (name "unconnected-(J1-Pad29)") (class "Default")
      (node (ref "J1") (pin "29") (pinfunction "29_29") (pintype "passive"))
    )
    (net (code "81") (name "unconnected-(J1-Pad30)") (class "Default")
      (node (ref "J1") (pin "30") (pinfunction "30_30") (pintype "passive"))
    )
    (net (code "82") (name "unconnected-(J1-Pad31)") (class "Default")
      (node (ref "J1") (pin "31") (pinfunction "31_31") (pintype "passive"))
    )
    (net (code "83") (name "unconnected-(J1-Pad32)") (class "Default")
      (node (ref "J1") (pin "32") (pinfunction "32_32") (pintype "passive"))
    )
    (net (code "84") (name "unconnected-(J1-Pad33)") (class "Default")
      (node (ref "J1") (pin "33") (pinfunction "33_33") (pintype "passive"))
    )
    (net (code "85") (name "unconnected-(J1-Pad34)") (class "Default")
      (node (ref "J1") (pin "34") (pinfunction "34_34") (pintype "passive"))
    )
    (net (code "86") (name "unconnected-(J1-Pad35)") (class "Default")
      (node (ref "J1") (pin "35") (pinfunction "35_35") (pintype "passive"))
    )
    (net (code "87") (name "unconnected-(J1-Pad36)") (class "Default")
      (node (ref "J1") (pin "36") (pinfunction "36_36") (pintype "passive"))
    )
    (net (code "88") (name "unconnected-(J1-Pad37)") (class "Default")
      (node (ref "J1") (pin "37") (pinfunction "37_37") (pintype "passive"))
    )
    (net (code "89") (name "unconnected-(J1-Pad38)") (class "Default")
      (node (ref "J1") (pin "38") (pinfunction "38_38") (pintype "passive"))
    )
    (net (code "90") (name "unconnected-(J1-Pad39)") (class "Default")
      (node (ref "J1") (pin "39") (pinfunction "39_39") (pintype "passive"))
    )
    (net (code "91") (name "unconnected-(J1-Pad40)") (class "Default")
      (node (ref "J1") (pin "40") (pinfunction "40_40") (pintype "passive"))
    )
    (net (code "92") (name "unconnected-(J1-Pad41)") (class "Default")
      (node (ref "J1") (pin "41") (pinfunction "41_41") (pintype "passive"))
    )
    (net (code "93") (name "unconnected-(J1-Pad43)") (class "Default")
      (node (ref "J1") (pin "43") (pinfunction "43_43") (pintype "passive"))
    )
    (net (code "94") (name "unconnected-(J1-Pad45)") (class "Default")
      (node (ref "J1") (pin "45") (pinfunction "45_45") (pintype "passive"))
    )
    (net (code "95") (name "unconnected-(J1-Pad46)") (class "Default")
      (node (ref "J1") (pin "46") (pinfunction "46_46") (pintype "passive"))
    )
    (net (code "96") (name "unconnected-(J1-Pad47)") (class "Default")
      (node (ref "J1") (pin "47") (pinfunction "47_47") (pintype "passive"))
    )
    (net (code "97") (name "unconnected-(J1-Pad48)") (class "Default")
      (node (ref "J1") (pin "48") (pinfunction "48_48") (pintype "passive"))
    )
    (net (code "98") (name "unconnected-(J1-Pad49)") (class "Default")
      (node (ref "J1") (pin "49") (pinfunction "49_49") (pintype "passive"))
    )
    (net (code "99") (name "unconnected-(J1-Pad50)") (class "Default")
      (node (ref "J1") (pin "50") (pinfunction "50_50") (pintype "passive"))
    )
    (net (code "100") (name "unconnected-(J1-Pad51)") (class "Default")
      (node (ref "J1") (pin "51") (pinfunction "51_51") (pintype "passive"))
    )
    (net (code "101") (name "unconnected-(J1-Pad52)") (class "Default")
      (node (ref "J1") (pin "52") (pinfunction "52_52") (pintype "passive"))
    )
    (net (code "102") (name "unconnected-(J2-Pad1)") (class "Default")
      (node (ref "J2") (pin "1") (pinfunction "1_1") (pintype "passive"))
    )
    (net (code "103") (name "unconnected-(J2-Pad2)") (class "Default")
      (node (ref "J2") (pin "2") (pinfunction "2_2") (pintype "passive"))
    )
    (net (code "104") (name "unconnected-(J2-Pad3)") (class "Default")
      (node (ref "J2") (pin "3") (pinfunction "3_3") (pintype "passive"))
    )
    (net (code "105") (name "unconnected-(J2-Pad4)") (class "Default")
      (node (ref "J2") (pin "4") (pinfunction "4_4") (pintype "passive"))
    )
    (net (code "106") (name "unconnected-(J2-Pad5)") (class "Default")
      (node (ref "J2") (pin "5") (pinfunction "5_5") (pintype "passive"))
    )
    (net (code "107") (name "unconnected-(J2-Pad6)") (class "Default")
      (node (ref "J2") (pin "6") (pinfunction "6_6") (pintype "passive"))
    )
    (net (code "108") (name "unconnected-(J2-Pad7)") (class "Default")
      (node (ref "J2") (pin "7") (pinfunction "7_7") (pintype "passive"))
    )
    (net (code "109") (name "unconnected-(J2-Pad8)") (class "Default")
      (node (ref "J2") (pin "8") (pinfunction "8_8") (pintype "passive"))
    )
    (net (code "110") (name "unconnected-(J2-Pad9)") (class "Default")
      (node (ref "J2") (pin "9") (pinfunction "9_9") (pintype "passive"))
    )
    (net (code "111") (name "unconnected-(J2-Pad11)") (class "Default")
      (node (ref "J2") (pin "11") (pinfunction "11_11") (pintype "passive"))
    )
    (net (code "112") (name "unconnected-(J2-Pad12)") (class "Default")
      (node (ref "J2") (pin "12") (pinfunction "12_12") (pintype "passive"))
    )
    (net (code "113") (name "unconnected-(J2-Pad23)") (class "Default")
      (node (ref "J2") (pin "23") (pinfunction "23_23") (pintype "passive"))
    )
    (net (code "114") (name "unconnected-(J2-Pad24)") (class "Default")
      (node (ref "J2") (pin "24") (pinfunction "24_24") (pintype "passive"))
    )
    (net (code "115") (name "unconnected-(J2-Pad32)") (class "Default")
      (node (ref "J2") (pin "32") (pinfunction "32_32") (pintype "passive"))
    )
    (net (code "116") (name "unconnected-(J2-Pad33)") (class "Default")
      (node (ref "J2") (pin "33") (pinfunction "33_33") (pintype "passive"))
    )
    (net (code "117") (name "unconnected-(J2-Pad34)") (class "Default")
      (node (ref "J2") (pin "34") (pinfunction "34_34") (pintype "passive"))
    )
    (net (code "118") (name "unconnected-(J2-Pad35)") (class "Default")
      (node (ref "J2") (pin "35") (pinfunction "35_35") (pintype "passive"))
    )
    (net (code "119") (name "unconnected-(J2-Pad36)") (class "Default")
      (node (ref "J2") (pin "36") (pinfunction "36_36") (pintype "passive"))
    )
    (net (code "120") (name "unconnected-(J2-Pad37)") (class "Default")
      (node (ref "J2") (pin "37") (pinfunction "37_37") (pintype "passive"))
    )
    (net (code "121") (name "unconnected-(J2-Pad38)") (class "Default")
      (node (ref "J2") (pin "38") (pinfunction "38_38") (pintype "passive"))
    )
    (net (code "122") (name "unconnected-(J2-Pad39)") (class "Default")
      (node (ref "J2") (pin "39") (pinfunction "39_39") (pintype "passive"))
    )
    (net (code "123") (name "unconnected-(J2-Pad40)") (class "Default")
      (node (ref "J2") (pin "40") (pinfunction "40_40") (pintype "passive"))
    )
    (net (code "124") (name "unconnected-(J2-Pad41)") (class "Default")
      (node (ref "J2") (pin "41") (pinfunction "41_41") (pintype "passive"))
    )
    (net (code "125") (name "unconnected-(J2-Pad42)") (class "Default")
      (node (ref "J2") (pin "42") (pinfunction "42_42") (pintype "passive"))
    )
    (net (code "126") (name "unconnected-(J2-Pad43)") (class "Default")
      (node (ref "J2") (pin "43") (pinfunction "43_43") (pintype "passive"))
    )
    (net (code "127") (name "unconnected-(J2-Pad44)") (class "Default")
      (node (ref "J2") (pin "44") (pinfunction "44_44") (pintype "passive"))
    )
    (net (code "128") (name "unconnected-(J2-Pad45)") (class "Default")
      (node (ref "J2") (pin "45") (pinfunction "45_45") (pintype "passive"))
    )
    (net (code "129") (name "unconnected-(J2-Pad46)") (class "Default")
      (node (ref "J2") (pin "46") (pinfunction "46_46") (pintype "passive"))
    )
    (net (code "130") (name "unconnected-(J2-Pad49)") (class "Default")
      (node (ref "J2") (pin "49") (pinfunction "49_49") (pintype "passive"))
    )
    (net (code "131") (name "unconnected-(J2-Pad50)") (class "Default")
      (node (ref "J2") (pin "50") (pinfunction "50_50") (pintype "passive"))
    )
    (net (code "132") (name "unconnected-(J2-Pad52)") (class "Default")
      (node (ref "J2") (pin "52") (pinfunction "52_52") (pintype "passive"))
    )
    (net (code "133") (name "unconnected-(PS1-VADJ-Pad12)") (class "Default")
      (node (ref "PS1") (pin "12") (pinfunction "VADJ_12") (pintype "passive"))
    )
    (net (code "134") (name "unconnected-(PS2-VADJ-Pad12)") (class "Default")
      (node (ref "PS2") (pin "12") (pinfunction "VADJ_12") (pintype "passive"))
    )
    (net (code "135") (name "unconnected-(U$1-5.5V-Pad5V)") (class "Default")
      (node (ref "U$1") (pin "5V") (pinfunction "5.5V_5V") (pintype "bidirectional"))
    )
    (net (code "136") (name "unconnected-(U$1-GND2-PadGND1)") (class "Default")
      (node (ref "U$1") (pin "GND1") (pinfunction "GND2_GND1") (pintype "bidirectional"))
    )
    (net (code "137") (name "unconnected-(U$1-Pad3.3V)") (class "Default")
      (node (ref "U$1") (pin "3.3V") (pinfunction "3.3V_3.3V") (pintype "bidirectional"))
    )
    (net (code "138") (name "unconnected-(U$1-PadAREF)") (class "Default")
      (node (ref "U$1") (pin "AREF") (pinfunction "AREF_AREF") (pintype "bidirectional"))
    )
    (net (code "139") (name "unconnected-(U$1-PadD2)") (class "Default")
      (node (ref "U$1") (pin "D2") (pinfunction "D2_D2") (pintype "bidirectional"))
    )
    (net (code "140") (name "unconnected-(U$1-PadD3)") (class "Default")
      (node (ref "U$1") (pin "D3") (pinfunction "D3_D3") (pintype "bidirectional"))
    )
    (net (code "141") (name "unconnected-(U$1-PadD4)") (class "Default")
      (node (ref "U$1") (pin "D4") (pinfunction "D4_D4") (pintype "bidirectional"))
    )
    (net (code "142") (name "unconnected-(U$1-PadICSP1)") (class "Default")
      (node (ref "U$1") (pin "ICSP1") (pinfunction "ICSP1_ICSP1") (pintype "bidirectional"))
    )
    (net (code "143") (name "unconnected-(U$1-PadICSP2)") (class "Default")
      (node (ref "U$1") (pin "ICSP2") (pinfunction "ICSP2_ICSP2") (pintype "bidirectional"))
    )
    (net (code "144") (name "unconnected-(U$1-PadICSP3)") (class "Default")
      (node (ref "U$1") (pin "ICSP3") (pinfunction "ICSP3_ICSP3") (pintype "bidirectional"))
    )
    (net (code "145") (name "unconnected-(U$1-PadICSP4)") (class "Default")
      (node (ref "U$1") (pin "ICSP4") (pinfunction "ICSP4_ICSP4") (pintype "bidirectional"))
    )
    (net (code "146") (name "unconnected-(U$1-PadICSP5)") (class "Default")
      (node (ref "U$1") (pin "ICSP5") (pinfunction "ICSP5_ICSP5") (pintype "bidirectional"))
    )
    (net (code "147") (name "unconnected-(U$1-PadICSP6)") (class "Default")
      (node (ref "U$1") (pin "ICSP6") (pinfunction "ICSP6_ICSP6") (pintype "bidirectional"))
    )
    (net (code "148") (name "unconnected-(U$1-PadRST)") (class "Default")
      (node (ref "U$1") (pin "RST") (pinfunction "RST_RST") (pintype "bidirectional"))
    )
    (net (code "149") (name "unconnected-(U$1-PadRST1)") (class "Default")
      (node (ref "U$1") (pin "RST1") (pinfunction "RST1_RST1") (pintype "bidirectional"))
    )
    (net (code "150") (name "unconnected-(U$1-PadRX1)") (class "Default")
      (node (ref "U$1") (pin "RX1") (pinfunction "RX1_RX1") (pintype "bidirectional"))
    )
    (net (code "151") (name "unconnected-(U$1-PadTX0)") (class "Default")
      (node (ref "U$1") (pin "TX0") (pinfunction "TX0_TX0") (pintype "bidirectional"))
    )
  )
)
